# dbLcdRtcUno.net
KiCad netlist of a schematic drawn in EAGLE
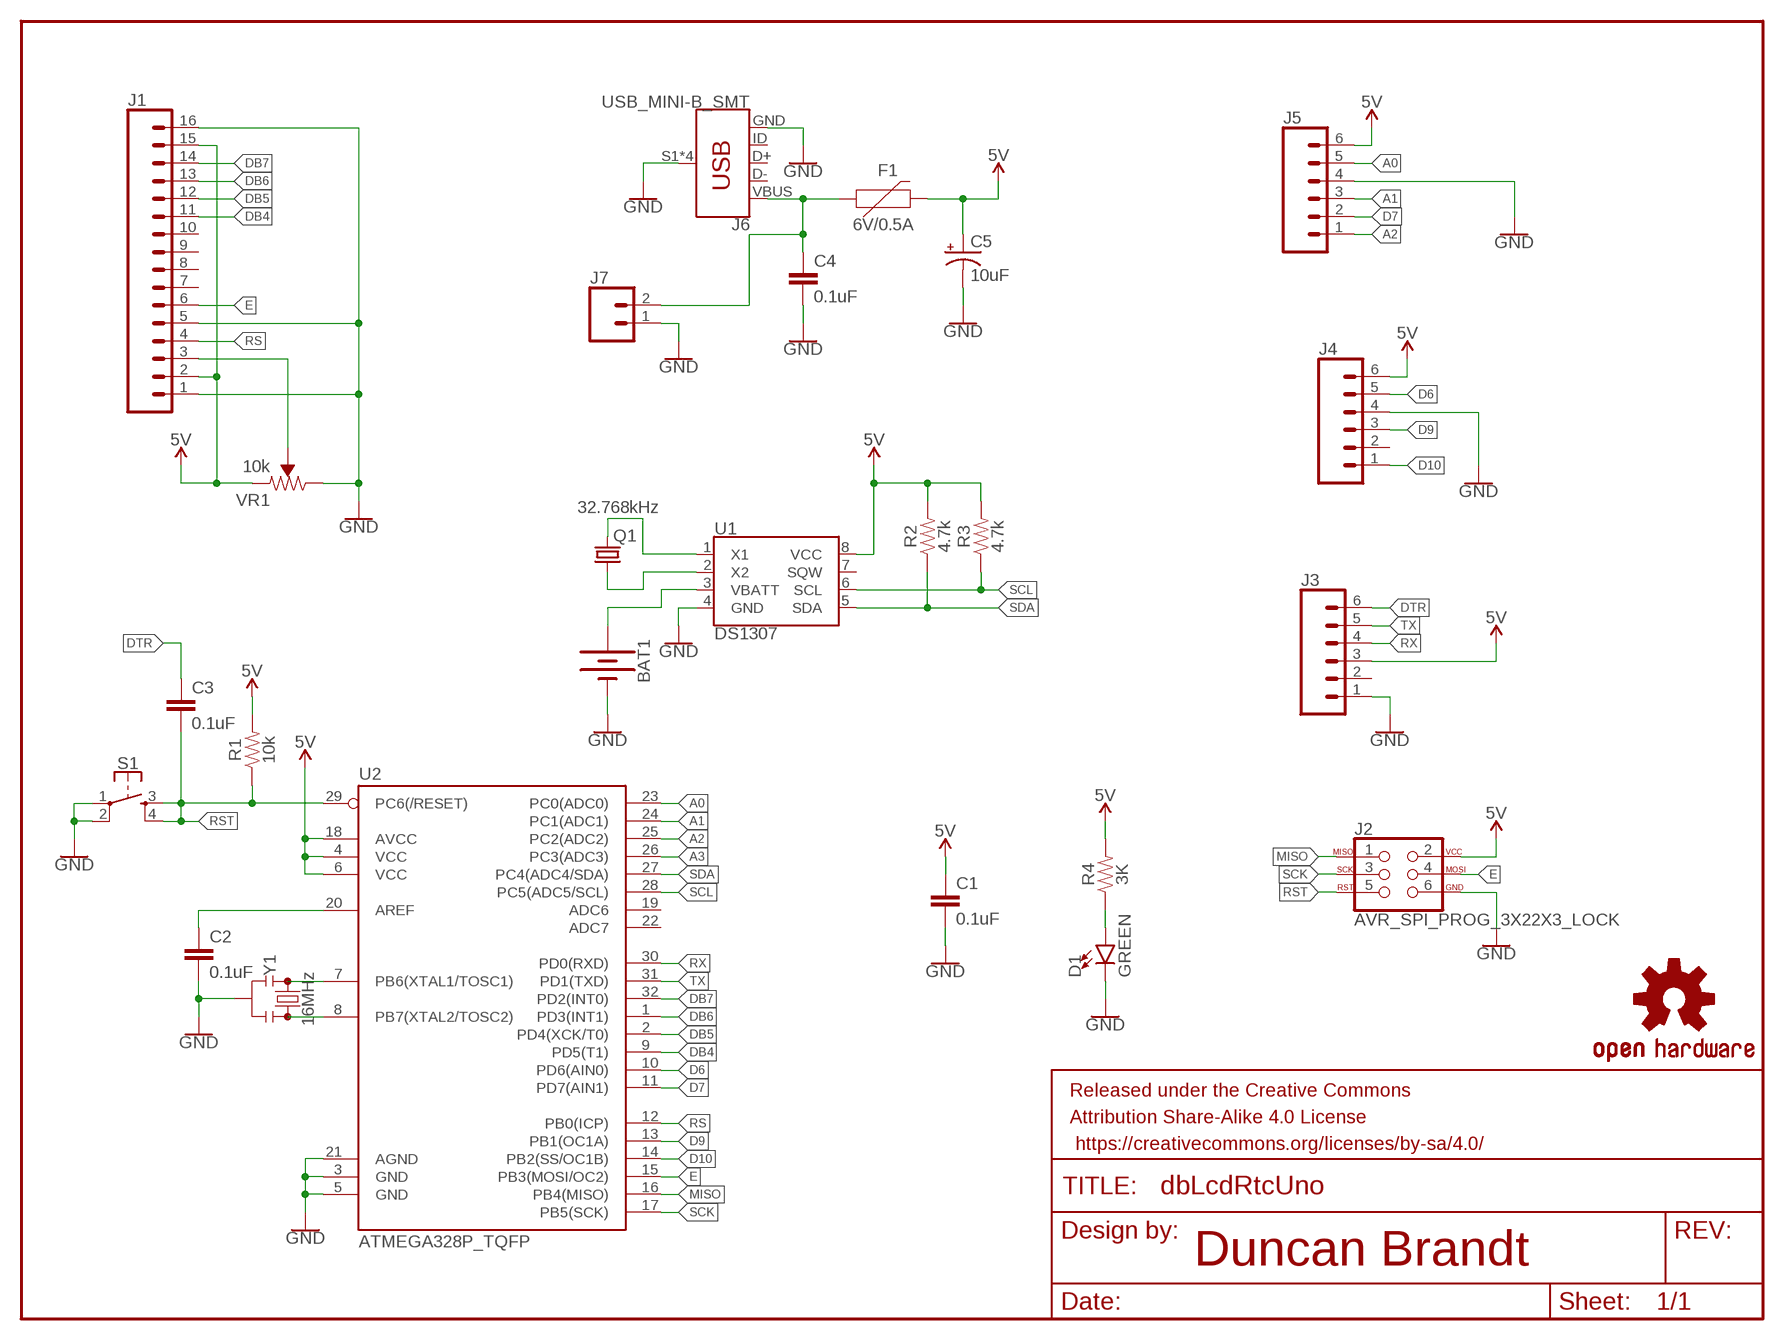
[diagram p0: schematic, sheet 1]

(export (version "E")
  (design (tool "Eeschema 10.0.6"))
  (components
    (comp (ref "BAT1")
      (value "BATTERY-12MM_PTH")
      (footprint "eagle-import:BATTCON_12MM_PTH")
      (libsource (lib "eagle-import") (part "BATTERY-12MM_PTH"))
    )
    (comp (ref "C1")
      (value "0.1uF")
      (footprint "eagle-import:0603")
      (libsource (lib "eagle-import") (part "0.1UF-0603-25V-5%"))
    )
    (comp (ref "C2")
      (value "0.1uF")
      (footprint "eagle-import:0603")
      (libsource (lib "eagle-import") (part "0.1UF-0603-25V-5%"))
    )
    (comp (ref "C3")
      (value "0.1uF")
      (footprint "eagle-import:0603")
      (libsource (lib "eagle-import") (part "0.1UF-0603-25V-5%"))
    )
    (comp (ref "C4")
      (value "0.1uF")
      (footprint "eagle-import:0603")
      (libsource (lib "eagle-import") (part "0.1UF-0603-25V-5%"))
    )
    (comp (ref "C5")
      (value "10uF")
      (footprint "eagle-import:EIA3216")
      (libsource (lib "eagle-import") (part "10UF-POLAR-EIA3216-16V-10%(TANT)"))
    )
    (comp (ref "D1")
      (value "GREEN")
      (footprint "eagle-import:LED-1206")
      (libsource (lib "eagle-import") (part "LED-GREEN1206"))
    )
    (comp (ref "F1")
      (value "6V/0.5A")
      (footprint "eagle-import:1206")
      (libsource (lib "eagle-import") (part "PPTC_HALF-AMP"))
    )
    (comp (ref "FRAME1")
      (value "FRAME-LETTER")
      (footprint "eagle-import:CREATIVE_COMMONS")
      (libsource (lib "eagle-import") (part "FRAME-LETTER"))
    )
    (comp (ref "J1")
      (value "CONN_16")
      (footprint "eagle-import:1X16")
      (libsource (lib "eagle-import") (part "CONN_16"))
    )
    (comp (ref "J2")
      (value "AVR_SPI_PROG_3X22X3_LOCK")
      (footprint "eagle-import:2X3_LOCK")
      (libsource (lib "eagle-import") (part "AVR_SPI_PROG_3X22X3_LOCK"))
    )
    (comp (ref "J3")
      (value "CONN_06SILK_FEMALE_PTH")
      (footprint "eagle-import:1X06")
      (libsource (lib "eagle-import") (part "CONN_06SILK_FEMALE_PTH"))
    )
    (comp (ref "J4")
      (value "CONN_06SILK_FEMALE_PTH")
      (footprint "eagle-import:1X06")
      (libsource (lib "eagle-import") (part "CONN_06SILK_FEMALE_PTH"))
    )
    (comp (ref "J5")
      (value "CONN_06SILK_FEMALE_PTH")
      (footprint "eagle-import:1X06")
      (libsource (lib "eagle-import") (part "CONN_06SILK_FEMALE_PTH"))
    )
    (comp (ref "J6")
      (value "USB_MINI-B_SMT")
      (footprint "eagle-import:USB-MINIB")
      (libsource (lib "eagle-import") (part "USB_MINI-B_SMT"))
    )
    (comp (ref "J7")
      (value "CONN_02")
      (footprint "eagle-import:1X02")
      (libsource (lib "eagle-import") (part "CONN_02"))
    )
    (comp (ref "LOGO1")
      (value "OSHW-LOGOL")
      (footprint "eagle-import:OSHW-LOGO-L")
      (libsource (lib "eagle-import") (part "OSHW-LOGOL"))
    )
    (comp (ref "Q1")
      (value "32.768kHz")
      (footprint "eagle-import:CRYSTAL-SMD-2X6-CYL")
      (libsource (lib "eagle-import") (part "CRYSTAL-32.768KHZSMD-2X6"))
    )
    (comp (ref "R1")
      (value "10k")
      (footprint "eagle-import:0603")
      (libsource (lib "eagle-import") (part "10KOHM-0603-1/10W-1%"))
    )
    (comp (ref "R2")
      (value "4.7k")
      (footprint "eagle-import:0603")
      (libsource (lib "eagle-import") (part "4.7KOHM-0603-1/10W-1%"))
    )
    (comp (ref "R3")
      (value "4.7k")
      (footprint "eagle-import:0603")
      (libsource (lib "eagle-import") (part "4.7KOHM-0603-1/10W-1%"))
    )
    (comp (ref "R4")
      (value "3K")
      (footprint "eagle-import:0603")
      (libsource (lib "eagle-import") (part "3KOHM-0603-1/10W-1%"))
    )
    (comp (ref "S1")
      (value "MOMENTARY-SWITCH-SPST-2-SMD-5.2MM")
      (footprint "eagle-import:TACTILE_SWITCH_SMD_5.2MM")
      (libsource (lib "eagle-import") (part "MOMENTARY-SWITCH-SPST-2-SMD-5.2MM"))
    )
    (comp (ref "U1")
      (value "DS1307")
      (footprint "eagle-import:SO08-0.15")
      (libsource (lib "eagle-import") (part "DS1307Z"))
    )
    (comp (ref "U2")
      (value "ATMEGA328P_TQFP")
      (footprint "eagle-import:TQFP32-08")
      (libsource (lib "eagle-import") (part "ATMEGA328P_TQFP"))
    )
    (comp (ref "VR1")
      (value "10k")
      (footprint "eagle-import:TRIMPOT-SMD-3MM-CLOSED")
      (libsource (lib "eagle-import") (part "TRIMPOT-SMD-3MM-CLOSED-1/8W-20%"))
    )
    (comp (ref "Y1")
      (value "16MHz")
      (footprint "eagle-import:RESONATOR-SMD-3.2X1.3")
      (libsource (lib "eagle-import") (part "RESONATOR-16MHZSMD_3.2X1.3"))
    )
  )
  (nets
    (net (code "1") (name "5V") (class "Default")
      (node (ref "C1") (pin "1") (pinfunction "1_1") (pintype "passive"))
      (node (ref "C5") (pin "+") (pinfunction "+_+") (pintype "passive"))
      (node (ref "F1") (pin "2") (pinfunction "2_2") (pintype "bidirectional"))
      (node (ref "J1") (pin "15") (pinfunction "15_15") (pintype "passive"))
      (node (ref "J1") (pin "2") (pinfunction "2_2") (pintype "passive"))
      (node (ref "J2") (pin "2") (pinfunction "2_2") (pintype "passive"))
      (node (ref "J3") (pin "3") (pinfunction "3_3") (pintype "passive"))
      (node (ref "J4") (pin "6") (pinfunction "6_6") (pintype "passive"))
      (node (ref "J5") (pin "6") (pinfunction "6_6") (pintype "passive"))
      (node (ref "R1") (pin "2") (pinfunction "2_2") (pintype "passive"))
      (node (ref "R2") (pin "2") (pinfunction "2_2") (pintype "passive"))
      (node (ref "R3") (pin "2") (pinfunction "2_2") (pintype "passive"))
      (node (ref "R4") (pin "2") (pinfunction "2_2") (pintype "passive"))
      (node (ref "U1") (pin "8") (pinfunction "VCC_8") (pintype "bidirectional"))
      (node (ref "U2") (pin "18") (pinfunction "AVCC_18") (pintype "bidirectional"))
      (node (ref "U2") (pin "4") (pinfunction "VCC_4") (pintype "bidirectional"))
      (node (ref "U2") (pin "6") (pinfunction "VCC_6") (pintype "bidirectional"))
      (node (ref "VR1") (pin "1") (pinfunction "CCW_1") (pintype "passive"))
    )
    (net (code "2") (name "A0") (class "Default")
      (node (ref "J5") (pin "5") (pinfunction "5_5") (pintype "passive"))
      (node (ref "U2") (pin "23") (pinfunction "PC0(ADC0)_23") (pintype "bidirectional"))
    )
    (net (code "3") (name "A1") (class "Default")
      (node (ref "J5") (pin "3") (pinfunction "3_3") (pintype "passive"))
      (node (ref "U2") (pin "24") (pinfunction "PC1(ADC1)_24") (pintype "bidirectional"))
    )
    (net (code "4") (name "A2") (class "Default")
      (node (ref "J5") (pin "1") (pinfunction "1_1") (pintype "passive"))
      (node (ref "U2") (pin "25") (pinfunction "PC2(ADC2)_25") (pintype "bidirectional"))
    )
    (net (code "5") (name "A3") (class "Default")
      (node (ref "U2") (pin "26") (pinfunction "PC3(ADC3)_26") (pintype "bidirectional"))
    )
    (net (code "6") (name "D6") (class "Default")
      (node (ref "J4") (pin "5") (pinfunction "5_5") (pintype "passive"))
      (node (ref "U2") (pin "10") (pinfunction "PD6(AIN0)_10") (pintype "bidirectional"))
    )
    (net (code "7") (name "D7") (class "Default")
      (node (ref "J5") (pin "2") (pinfunction "2_2") (pintype "passive"))
      (node (ref "U2") (pin "11") (pinfunction "PD7(AIN1)_11") (pintype "bidirectional"))
    )
    (net (code "8") (name "D9") (class "Default")
      (node (ref "J4") (pin "3") (pinfunction "3_3") (pintype "passive"))
      (node (ref "U2") (pin "13") (pinfunction "PB1(OC1A)_13") (pintype "bidirectional"))
    )
    (net (code "9") (name "D10") (class "Default")
      (node (ref "J4") (pin "1") (pinfunction "1_1") (pintype "passive"))
      (node (ref "U2") (pin "14") (pinfunction "PB2(SS/OC1B)_14") (pintype "bidirectional"))
    )
    (net (code "10") (name "DB4") (class "Default")
      (node (ref "J1") (pin "11") (pinfunction "11_11") (pintype "passive"))
      (node (ref "U2") (pin "9") (pinfunction "PD5(T1)_9") (pintype "bidirectional"))
    )
    (net (code "11") (name "DB5") (class "Default")
      (node (ref "J1") (pin "12") (pinfunction "12_12") (pintype "passive"))
      (node (ref "U2") (pin "2") (pinfunction "PD4(XCK/T0)_2") (pintype "bidirectional"))
    )
    (net (code "12") (name "DB6") (class "Default")
      (node (ref "J1") (pin "13") (pinfunction "13_13") (pintype "passive"))
      (node (ref "U2") (pin "1") (pinfunction "PD3(INT1)_1") (pintype "bidirectional"))
    )
    (net (code "13") (name "DB7") (class "Default")
      (node (ref "J1") (pin "14") (pinfunction "14_14") (pintype "passive"))
      (node (ref "U2") (pin "32") (pinfunction "PD2(INT0)_32") (pintype "bidirectional"))
    )
    (net (code "14") (name "DTR") (class "Default")
      (node (ref "C3") (pin "1") (pinfunction "1_1") (pintype "passive"))
      (node (ref "J3") (pin "6") (pinfunction "6_6") (pintype "passive"))
    )
    (net (code "15") (name "E") (class "Default")
      (node (ref "J1") (pin "6") (pinfunction "6_6") (pintype "passive"))
      (node (ref "J2") (pin "4") (pinfunction "4_4") (pintype "passive"))
      (node (ref "U2") (pin "15") (pinfunction "PB3(MOSI/OC2)_15") (pintype "bidirectional"))
    )
    (net (code "16") (name "GND") (class "Default")
      (node (ref "BAT1") (pin "GND") (pinfunction "-_GND") (pintype "power_in"))
      (node (ref "C1") (pin "2") (pinfunction "2_2") (pintype "passive"))
      (node (ref "C2") (pin "2") (pinfunction "2_2") (pintype "passive"))
      (node (ref "C4") (pin "2") (pinfunction "2_2") (pintype "passive"))
      (node (ref "C5") (pin "-") (pinfunction "-_-") (pintype "passive"))
      (node (ref "D1") (pin "C") (pinfunction "C_C") (pintype "passive"))
      (node (ref "J1") (pin "1") (pinfunction "1_1") (pintype "passive"))
      (node (ref "J1") (pin "16") (pinfunction "16_16") (pintype "passive"))
      (node (ref "J1") (pin "5") (pinfunction "5_5") (pintype "passive"))
      (node (ref "J2") (pin "6") (pinfunction "6_6") (pintype "passive"))
      (node (ref "J3") (pin "1") (pinfunction "1_1") (pintype "passive"))
      (node (ref "J4") (pin "4") (pinfunction "4_4") (pintype "passive"))
      (node (ref "J5") (pin "4") (pinfunction "4_4") (pintype "passive"))
      (node (ref "J6") (pin "GND") (pinfunction "GND_GND") (pintype "power_in"))
      (node (ref "J6") (pin "S1") (pinfunction "SHIELD_S1") (pintype "bidirectional"))
      (node (ref "J6") (pin "S2") (pinfunction "SHIELD_S2") (pintype "bidirectional"))
      (node (ref "J6") (pin "S3") (pinfunction "SHIELD_S3") (pintype "bidirectional"))
      (node (ref "J6") (pin "S4") (pinfunction "SHIELD_S4") (pintype "bidirectional"))
      (node (ref "J7") (pin "1") (pinfunction "1_1") (pintype "passive"))
      (node (ref "S1") (pin "1") (pinfunction "1_1") (pintype "passive"))
      (node (ref "S1") (pin "2") (pinfunction "2_2") (pintype "passive"))
      (node (ref "U1") (pin "4") (pinfunction "GND_4") (pintype "bidirectional"))
      (node (ref "U2") (pin "21") (pinfunction "AGND_21") (pintype "bidirectional"))
      (node (ref "U2") (pin "3") (pinfunction "GND_3") (pintype "bidirectional"))
      (node (ref "U2") (pin "5") (pinfunction "GND_5") (pintype "bidirectional"))
      (node (ref "VR1") (pin "3") (pinfunction "CW_3") (pintype "passive"))
      (node (ref "Y1") (pin "2") (pinfunction "2_2") (pintype "passive"))
    )
    (net (code "17") (name "MISO") (class "Default")
      (node (ref "J2") (pin "1") (pinfunction "1_1") (pintype "passive"))
      (node (ref "U2") (pin "16") (pinfunction "PB4(MISO)_16") (pintype "bidirectional"))
    )
    (net (code "18") (name "Net-(BAT1-+)") (class "Default")
      (node (ref "BAT1") (pin "VCC@1") (pinfunction "+_VCC@1") (pintype "power_in"))
      (node (ref "U1") (pin "3") (pinfunction "VBATT_3") (pintype "bidirectional"))
    )
    (net (code "19") (name "Net-(C4-Pad1)") (class "Default")
      (node (ref "C4") (pin "1") (pinfunction "1_1") (pintype "passive"))
      (node (ref "F1") (pin "1") (pinfunction "1_1") (pintype "bidirectional"))
      (node (ref "J6") (pin "VBUS") (pinfunction "VBUS_VBUS") (pintype "power_in"))
      (node (ref "J7") (pin "2") (pinfunction "2_2") (pintype "passive"))
    )
    (net (code "20") (name "Net-(D1-PadA)") (class "Default")
      (node (ref "D1") (pin "A") (pinfunction "A_A") (pintype "passive"))
      (node (ref "R4") (pin "1") (pinfunction "1_1") (pintype "passive"))
    )
    (net (code "21") (name "Net-(Q1-1)") (class "Default")
      (node (ref "Q1") (pin "X1") (pinfunction "1_X1") (pintype "passive"))
      (node (ref "U1") (pin "2") (pinfunction "X2_2") (pintype "bidirectional"))
    )
    (net (code "22") (name "Net-(Q1-2)") (class "Default")
      (node (ref "Q1") (pin "X2") (pinfunction "2_X2") (pintype "passive"))
      (node (ref "U1") (pin "1") (pinfunction "X1_1") (pintype "bidirectional"))
    )
    (net (code "23") (name "Net-(U2-AREF)") (class "Default")
      (node (ref "C2") (pin "1") (pinfunction "1_1") (pintype "passive"))
      (node (ref "U2") (pin "20") (pinfunction "AREF_20") (pintype "bidirectional"))
    )
    (net (code "24") (name "Net-(U2-PB6(XTAL1{slash}TOSC1))") (class "Default")
      (node (ref "U2") (pin "7") (pinfunction "PB6(XTAL1/TOSC1)_7") (pintype "bidirectional"))
      (node (ref "Y1") (pin "1") (pinfunction "1_1") (pintype "passive"))
    )
    (net (code "25") (name "Net-(U2-PB7(XTAL2{slash}TOSC2))") (class "Default")
      (node (ref "U2") (pin "8") (pinfunction "PB7(XTAL2/TOSC2)_8") (pintype "bidirectional"))
      (node (ref "Y1") (pin "3") (pinfunction "3_3") (pintype "passive"))
    )
    (net (code "26") (name "Net-(VR1-WIPER)") (class "Default")
      (node (ref "J1") (pin "3") (pinfunction "3_3") (pintype "passive"))
      (node (ref "VR1") (pin "2") (pinfunction "WIPER_2") (pintype "passive"))
    )
    (net (code "27") (name "RS") (class "Default")
      (node (ref "J1") (pin "4") (pinfunction "4_4") (pintype "passive"))
      (node (ref "U2") (pin "12") (pinfunction "PB0(ICP)_12") (pintype "bidirectional"))
    )
    (net (code "28") (name "RST") (class "Default")
      (node (ref "C3") (pin "2") (pinfunction "2_2") (pintype "passive"))
      (node (ref "J2") (pin "5") (pinfunction "5_5") (pintype "passive"))
      (node (ref "R1") (pin "1") (pinfunction "1_1") (pintype "passive"))
      (node (ref "S1") (pin "3") (pinfunction "3_3") (pintype "passive"))
      (node (ref "S1") (pin "4") (pinfunction "4_4") (pintype "passive"))
      (node (ref "U2") (pin "29") (pinfunction "PC6(/RESET)_29") (pintype "bidirectional"))
    )
    (net (code "29") (name "RX") (class "Default")
      (node (ref "J3") (pin "4") (pinfunction "4_4") (pintype "passive"))
      (node (ref "U2") (pin "30") (pinfunction "PD0(RXD)_30") (pintype "bidirectional"))
    )
    (net (code "30") (name "SCK") (class "Default")
      (node (ref "J2") (pin "3") (pinfunction "3_3") (pintype "passive"))
      (node (ref "U2") (pin "17") (pinfunction "PB5(SCK)_17") (pintype "bidirectional"))
    )
    (net (code "31") (name "SCL") (class "Default")
      (node (ref "R3") (pin "1") (pinfunction "1_1") (pintype "passive"))
      (node (ref "U1") (pin "6") (pinfunction "SCL_6") (pintype "bidirectional"))
      (node (ref "U2") (pin "28") (pinfunction "PC5(ADC5/SCL)_28") (pintype "bidirectional"))
    )
    (net (code "32") (name "SDA") (class "Default")
      (node (ref "R2") (pin "1") (pinfunction "1_1") (pintype "passive"))
      (node (ref "U1") (pin "5") (pinfunction "SDA_5") (pintype "bidirectional"))
      (node (ref "U2") (pin "27") (pinfunction "PC4(ADC4/SDA)_27") (pintype "bidirectional"))
    )
    (net (code "33") (name "TX") (class "Default")
      (node (ref "J3") (pin "5") (pinfunction "5_5") (pintype "passive"))
      (node (ref "U2") (pin "31") (pinfunction "PD1(TXD)_31") (pintype "bidirectional"))
    )
    (net (code "34") (name "unconnected-(J1-Pad7)") (class "Default")
      (node (ref "J1") (pin "7") (pinfunction "7_7") (pintype "passive"))
    )
    (net (code "35") (name "unconnected-(J1-Pad8)") (class "Default")
      (node (ref "J1") (pin "8") (pinfunction "8_8") (pintype "passive"))
    )
    (net (code "36") (name "unconnected-(J1-Pad9)") (class "Default")
      (node (ref "J1") (pin "9") (pinfunction "9_9") (pintype "passive"))
    )
    (net (code "37") (name "unconnected-(J1-Pad10)") (class "Default")
      (node (ref "J1") (pin "10") (pinfunction "10_10") (pintype "passive"))
    )
    (net (code "38") (name "unconnected-(J3-Pad2)") (class "Default")
      (node (ref "J3") (pin "2") (pinfunction "2_2") (pintype "passive"))
    )
    (net (code "39") (name "unconnected-(J4-Pad2)") (class "Default")
      (node (ref "J4") (pin "2") (pinfunction "2_2") (pintype "passive"))
    )
    (net (code "40") (name "unconnected-(J6-PadD+)") (class "Default")
      (node (ref "J6") (pin "D+") (pinfunction "D+_D+") (pintype "bidirectional"))
    )
    (net (code "41") (name "unconnected-(J6-PadD-)") (class "Default")
      (node (ref "J6") (pin "D-") (pinfunction "D-_D-") (pintype "bidirectional"))
    )
    (net (code "42") (name "unconnected-(J6-PadID)") (class "Default")
      (node (ref "J6") (pin "ID") (pinfunction "ID_ID") (pintype "bidirectional"))
    )
    (net (code "43") (name "unconnected-(U1-SQW-Pad7)") (class "Default")
      (node (ref "U1") (pin "7") (pinfunction "SQW_7") (pintype "bidirectional"))
    )
    (net (code "44") (name "unconnected-(U2-ADC6-Pad19)") (class "Default")
      (node (ref "U2") (pin "19") (pinfunction "ADC6_19") (pintype "bidirectional"))
    )
    (net (code "45") (name "unconnected-(U2-ADC7-Pad22)") (class "Default")
      (node (ref "U2") (pin "22") (pinfunction "ADC7_22") (pintype "bidirectional"))
    )
  )
)
